# Steppers.net
KiCad netlist of a schematic drawn in Altium Designer
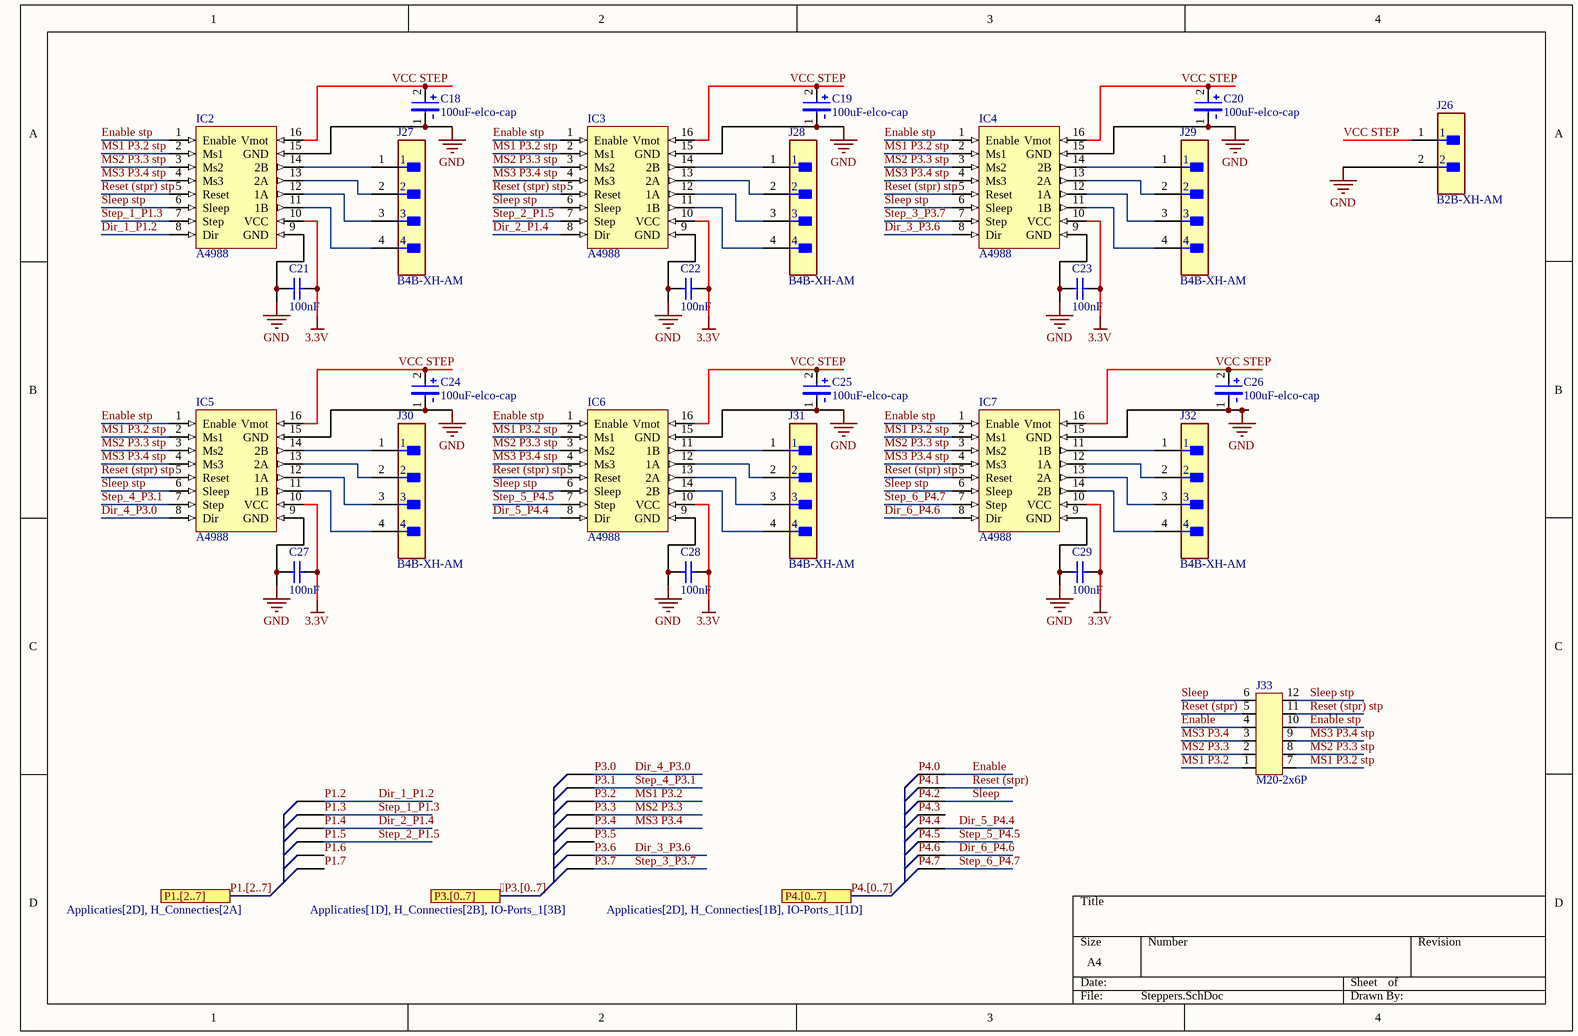
[diagram p0: Steppers.SchDoc]

(export (version "E")
  (design (tool "Eeschema 10.0.6"))
  (components
    (comp (ref "C18")
      (value "100uF-elco-cap")
      (footprint "SMD-ELCO-CAP")
      (description "Max 35V")
      (libsource (lib "Eigen_schemas") (part "100uF-elco-cap"))
    )
    (comp (ref "C19")
      (value "100uF-elco-cap")
      (footprint "SMD-ELCO-CAP")
      (description "Max 35V")
      (libsource (lib "Eigen_schemas") (part "100uF-elco-cap"))
    )
    (comp (ref "C20")
      (value "100uF-elco-cap")
      (footprint "SMD-ELCO-CAP")
      (description "Max 35V")
      (libsource (lib "Eigen_schemas") (part "100uF-elco-cap"))
    )
    (comp (ref "C21")
      (value "100nF")
      (footprint "CAPC1608X90X35LL15T15")
      (fields
        (field (name "MANUFACTURER") "AVX Interconnect / Elco")
        (field (name "PART NUMBER") "0603ZC101KAT2A")
      )
      (libsource (lib "Altium Content Vault") (part "CAP"))
    )
    (comp (ref "C22")
      (value "100nF")
      (footprint "CAPC1608X90X35LL15T15")
      (fields
        (field (name "MANUFACTURER") "AVX Interconnect / Elco")
        (field (name "PART NUMBER") "0603ZC101KAT2A")
      )
      (libsource (lib "Altium Content Vault") (part "CAP"))
    )
    (comp (ref "C23")
      (value "100nF")
      (footprint "CAPC1608X90X35LL15T15")
      (fields
        (field (name "MANUFACTURER") "AVX Interconnect / Elco")
        (field (name "PART NUMBER") "0603ZC101KAT2A")
      )
      (libsource (lib "Altium Content Vault") (part "CAP"))
    )
    (comp (ref "C24")
      (value "100uF-elco-cap")
      (footprint "SMD-ELCO-CAP")
      (description "Max 35V")
      (libsource (lib "Eigen_schemas") (part "100uF-elco-cap"))
    )
    (comp (ref "C25")
      (value "100uF-elco-cap")
      (footprint "SMD-ELCO-CAP")
      (description "Max 35V")
      (libsource (lib "Eigen_schemas") (part "100uF-elco-cap"))
    )
    (comp (ref "C26")
      (value "100uF-elco-cap")
      (footprint "SMD-ELCO-CAP")
      (description "Max 35V")
      (libsource (lib "Eigen_schemas") (part "100uF-elco-cap"))
    )
    (comp (ref "C27")
      (value "100nF")
      (footprint "CAPC1608X90X35LL15T15")
      (fields
        (field (name "MANUFACTURER") "AVX Interconnect / Elco")
        (field (name "PART NUMBER") "0603ZC101KAT2A")
      )
      (libsource (lib "Altium Content Vault") (part "CAP"))
    )
    (comp (ref "C28")
      (value "100nF")
      (footprint "CAPC1608X90X35LL15T15")
      (fields
        (field (name "MANUFACTURER") "AVX Interconnect / Elco")
        (field (name "PART NUMBER") "0603ZC101KAT2A")
      )
      (libsource (lib "Altium Content Vault") (part "CAP"))
    )
    (comp (ref "C29")
      (value "100nF")
      (footprint "CAPC1608X90X35LL15T15")
      (fields
        (field (name "MANUFACTURER") "AVX Interconnect / Elco")
        (field (name "PART NUMBER") "0603ZC101KAT2A")
      )
      (libsource (lib "Altium Content Vault") (part "CAP"))
    )
    (comp (ref "IC2")
      (value "A4988")
      (footprint "A4988")
      (description "stappenmotor driver")
      (libsource (lib "Eigen_schemas") (part "A4988"))
    )
    (comp (ref "IC3")
      (value "A4988")
      (footprint "A4988")
      (description "stappenmotor driver")
      (libsource (lib "Eigen_schemas") (part "A4988"))
    )
    (comp (ref "IC4")
      (value "A4988")
      (footprint "A4988")
      (description "stappenmotor driver")
      (libsource (lib "Eigen_schemas") (part "A4988"))
    )
    (comp (ref "IC5")
      (value "A4988")
      (footprint "A4988")
      (description "stappenmotor driver")
      (libsource (lib "Eigen_schemas") (part "A4988"))
    )
    (comp (ref "IC6")
      (value "A4988")
      (footprint "A4988")
      (description "stappenmotor driver")
      (libsource (lib "") (part "A4988_1"))
    )
    (comp (ref "IC7")
      (value "A4988")
      (footprint "A4988")
      (description "stappenmotor driver")
      (libsource (lib "") (part "A4988_1"))
    )
    (comp (ref "J26")
      (value "B2B-XH-AM")
      (footprint "FP-B2B-XH-AM_LF_SN-MFG")
      (description "CONN HEADER VERT 2POS 2.5MM")
      (libsource (lib "Altium Content Vault") (part "3bc925449376181038e59eaffc5286c"))
    )
    (comp (ref "J27")
      (value "B4B-XH-AM")
      (footprint "FP-B4B-XH-A_LF_SN-MFG")
      (description "CONN HEADER VERT 4POS 2.5MM")
      (libsource (lib "Altium Content Vault") (part "299a8cea1bdcbc3624fe62c390fa72c"))
    )
    (comp (ref "J28")
      (value "B4B-XH-AM")
      (footprint "FP-B4B-XH-A_LF_SN-MFG")
      (description "CONN HEADER VERT 4POS 2.5MM")
      (libsource (lib "Altium Content Vault") (part "299a8cea1bdcbc3624fe62c390fa72c"))
    )
    (comp (ref "J29")
      (value "B4B-XH-AM")
      (footprint "FP-B4B-XH-A_LF_SN-MFG")
      (description "CONN HEADER VERT 4POS 2.5MM")
      (libsource (lib "Altium Content Vault") (part "299a8cea1bdcbc3624fe62c390fa72c"))
    )
    (comp (ref "J30")
      (value "B4B-XH-AM")
      (footprint "FP-B4B-XH-A_LF_SN-MFG")
      (description "CONN HEADER VERT 4POS 2.5MM")
      (libsource (lib "Altium Content Vault") (part "299a8cea1bdcbc3624fe62c390fa72c"))
    )
    (comp (ref "J31")
      (value "B4B-XH-AM")
      (footprint "FP-B4B-XH-A_LF_SN-MFG")
      (description "CONN HEADER VERT 4POS 2.5MM")
      (libsource (lib "Altium Content Vault") (part "299a8cea1bdcbc3624fe62c390fa72c"))
    )
    (comp (ref "J32")
      (value "B4B-XH-AM")
      (footprint "FP-B4B-XH-A_LF_SN-MFG")
      (description "CONN HEADER VERT 4POS 2.5MM")
      (libsource (lib "Altium Content Vault") (part "299a8cea1bdcbc3624fe62c390fa72c"))
    )
    (comp (ref "J33")
      (value "M20-2x6P")
      (footprint "M20-2x6PIN")
      (libsource (lib "Eigen_schemas") (part "M20-2x6P"))
    )
  )
  (nets
    (net (code "9") (name "/P3.0") (class "Default")
      (node (ref "IC5") (pin "8") (pinfunction "Dir_8") (pintype "input"))
    )
    (net (code "10") (name "/P3.1") (class "Default")
      (node (ref "IC5") (pin "7") (pinfunction "Step_7") (pintype "input"))
    )
    (net (code "11") (name "/P3.2") (class "Default")
      (node (ref "J33") (pin "1") (pinfunction "9_1") (pintype "passive"))
    )
    (net (code "12") (name "/P3.3") (class "Default")
      (node (ref "J33") (pin "2") (pinfunction "10_2") (pintype "passive"))
    )
    (net (code "13") (name "/P3.4") (class "Default")
      (node (ref "J33") (pin "3") (pinfunction "11_3") (pintype "passive"))
    )
    (net (code "15") (name "/P3.6") (class "Default")
      (node (ref "IC4") (pin "8") (pinfunction "Dir_8") (pintype "input"))
    )
    (net (code "16") (name "/P3.7") (class "Default")
      (node (ref "IC4") (pin "7") (pinfunction "Step_7") (pintype "input"))
    )
    (net (code "18") (name "/Enable stp") (class "Default")
      (node (ref "IC2") (pin "1") (pinfunction "Enable_1") (pintype "input"))
      (node (ref "IC3") (pin "1") (pinfunction "Enable_1") (pintype "input"))
      (node (ref "IC4") (pin "1") (pinfunction "Enable_1") (pintype "input"))
      (node (ref "IC5") (pin "1") (pinfunction "Enable_1") (pintype "input"))
      (node (ref "IC6") (pin "1") (pinfunction "Enable_1") (pintype "input"))
      (node (ref "IC7") (pin "1") (pinfunction "Enable_1") (pintype "input"))
      (node (ref "J33") (pin "10") (pinfunction "10_10") (pintype "passive"))
    )
    (net (code "19") (name "/MS1 P3.2 stp") (class "Default")
      (node (ref "IC2") (pin "2") (pinfunction "Ms1_2") (pintype "input"))
      (node (ref "IC3") (pin "2") (pinfunction "Ms1_2") (pintype "input"))
      (node (ref "IC4") (pin "2") (pinfunction "Ms1_2") (pintype "input"))
      (node (ref "IC5") (pin "2") (pinfunction "Ms1_2") (pintype "input"))
      (node (ref "IC6") (pin "2") (pinfunction "Ms1_2") (pintype "input"))
      (node (ref "IC7") (pin "2") (pinfunction "Ms1_2") (pintype "input"))
      (node (ref "J33") (pin "7") (pinfunction "7_7") (pintype "passive"))
    )
    (net (code "20") (name "/MS2 P3.3 stp") (class "Default")
      (node (ref "IC2") (pin "3") (pinfunction "Ms2_3") (pintype "input"))
      (node (ref "IC3") (pin "3") (pinfunction "Ms2_3") (pintype "input"))
      (node (ref "IC4") (pin "3") (pinfunction "Ms2_3") (pintype "input"))
      (node (ref "IC5") (pin "3") (pinfunction "Ms2_3") (pintype "input"))
      (node (ref "IC6") (pin "3") (pinfunction "Ms2_3") (pintype "input"))
      (node (ref "IC7") (pin "3") (pinfunction "Ms2_3") (pintype "input"))
      (node (ref "J33") (pin "8") (pinfunction "8_8") (pintype "passive"))
    )
    (net (code "21") (name "/MS3 P3.4 stp") (class "Default")
      (node (ref "IC2") (pin "4") (pinfunction "Ms3_4") (pintype "input"))
      (node (ref "IC3") (pin "4") (pinfunction "Ms3_4") (pintype "input"))
      (node (ref "IC4") (pin "4") (pinfunction "Ms3_4") (pintype "input"))
      (node (ref "IC5") (pin "4") (pinfunction "Ms3_4") (pintype "input"))
      (node (ref "IC6") (pin "4") (pinfunction "Ms3_4") (pintype "input"))
      (node (ref "IC7") (pin "4") (pinfunction "Ms3_4") (pintype "input"))
      (node (ref "J33") (pin "9") (pinfunction "9_9") (pintype "passive"))
    )
    (net (code "22") (name "/P1.2") (class "Default")
      (node (ref "IC2") (pin "8") (pinfunction "Dir_8") (pintype "input"))
    )
    (net (code "23") (name "/P1.3") (class "Default")
      (node (ref "IC2") (pin "7") (pinfunction "Step_7") (pintype "input"))
    )
    (net (code "24") (name "/P1.4") (class "Default")
      (node (ref "IC3") (pin "8") (pinfunction "Dir_8") (pintype "input"))
    )
    (net (code "25") (name "/P1.5") (class "Default")
      (node (ref "IC3") (pin "7") (pinfunction "Step_7") (pintype "input"))
    )
    (net (code "29") (name "/P4.0") (class "Default")
      (node (ref "J33") (pin "4") (pinfunction "12_4") (pintype "passive"))
    )
    (net (code "30") (name "/P4.1") (class "Default")
      (node (ref "J33") (pin "5") (pinfunction "13_5") (pintype "passive"))
    )
    (net (code "31") (name "/P4.2") (class "Default")
      (node (ref "J33") (pin "6") (pinfunction "14_6") (pintype "passive"))
    )
    (net (code "33") (name "/P4.4") (class "Default")
      (node (ref "IC6") (pin "8") (pinfunction "Dir_8") (pintype "input"))
    )
    (net (code "34") (name "/P4.5") (class "Default")
      (node (ref "IC6") (pin "7") (pinfunction "Step_7") (pintype "input"))
    )
    (net (code "35") (name "/P4.6") (class "Default")
      (node (ref "IC7") (pin "8") (pinfunction "Dir_8") (pintype "input"))
    )
    (net (code "36") (name "/P4.7") (class "Default")
      (node (ref "IC7") (pin "7") (pinfunction "Step_7") (pintype "input"))
    )
    (net (code "38") (name "/Reset (stpr) stp") (class "Default")
      (node (ref "IC2") (pin "5") (pinfunction "Reset_5") (pintype "input"))
      (node (ref "IC3") (pin "5") (pinfunction "Reset_5") (pintype "input"))
      (node (ref "IC4") (pin "5") (pinfunction "Reset_5") (pintype "input"))
      (node (ref "IC5") (pin "5") (pinfunction "Reset_5") (pintype "input"))
      (node (ref "IC6") (pin "5") (pinfunction "Reset_5") (pintype "input"))
      (node (ref "IC7") (pin "5") (pinfunction "Reset_5") (pintype "input"))
      (node (ref "J33") (pin "11") (pinfunction "11_11") (pintype "passive"))
    )
    (net (code "39") (name "/Sleep stp") (class "Default")
      (node (ref "IC2") (pin "6") (pinfunction "Sleep_6") (pintype "input"))
      (node (ref "IC3") (pin "6") (pinfunction "Sleep_6") (pintype "input"))
      (node (ref "IC4") (pin "6") (pinfunction "Sleep_6") (pintype "input"))
      (node (ref "IC5") (pin "6") (pinfunction "Sleep_6") (pintype "input"))
      (node (ref "IC6") (pin "6") (pinfunction "Sleep_6") (pintype "input"))
      (node (ref "IC7") (pin "6") (pinfunction "Sleep_6") (pintype "input"))
      (node (ref "J33") (pin "12") (pinfunction "12_12") (pintype "passive"))
    )
    (net (code "40") (name "/VCC STEP") (class "Default")
      (node (ref "C18") (pin "2") (pinfunction "5_2") (pintype "passive"))
      (node (ref "C19") (pin "2") (pinfunction "5_2") (pintype "passive"))
      (node (ref "C20") (pin "2") (pinfunction "5_2") (pintype "passive"))
      (node (ref "C24") (pin "2") (pinfunction "5_2") (pintype "passive"))
      (node (ref "C25") (pin "2") (pinfunction "5_2") (pintype "passive"))
      (node (ref "C26") (pin "2") (pinfunction "5_2") (pintype "passive"))
      (node (ref "IC2") (pin "16") (pinfunction "Vmot_16") (pintype "input"))
      (node (ref "IC3") (pin "16") (pinfunction "Vmot_16") (pintype "input"))
      (node (ref "IC4") (pin "16") (pinfunction "Vmot_16") (pintype "input"))
      (node (ref "IC5") (pin "16") (pinfunction "Vmot_16") (pintype "input"))
      (node (ref "IC6") (pin "16") (pinfunction "Vmot_16") (pintype "input"))
      (node (ref "IC7") (pin "16") (pinfunction "Vmot_16") (pintype "input"))
      (node (ref "J26") (pin "1") (pinfunction "1_1") (pintype "passive"))
    )
    (net (code "41") (name "3.3V") (class "Default")
      (node (ref "C21") (pin "1") (pinfunction "1_1") (pintype "passive"))
      (node (ref "C22") (pin "1") (pinfunction "1_1") (pintype "passive"))
      (node (ref "C23") (pin "1") (pinfunction "1_1") (pintype "passive"))
      (node (ref "C27") (pin "1") (pinfunction "1_1") (pintype "passive"))
      (node (ref "C28") (pin "1") (pinfunction "1_1") (pintype "passive"))
      (node (ref "C29") (pin "1") (pinfunction "1_1") (pintype "passive"))
      (node (ref "IC2") (pin "10") (pinfunction "VCC_10") (pintype "input"))
      (node (ref "IC3") (pin "10") (pinfunction "VCC_10") (pintype "input"))
      (node (ref "IC4") (pin "10") (pinfunction "VCC_10") (pintype "input"))
      (node (ref "IC5") (pin "10") (pinfunction "VCC_10") (pintype "input"))
      (node (ref "IC6") (pin "10") (pinfunction "VCC_10") (pintype "input"))
      (node (ref "IC7") (pin "10") (pinfunction "VCC_10") (pintype "input"))
    )
    (net (code "42") (name "GND") (class "Default")
      (node (ref "C18") (pin "1") (pinfunction "4_1") (pintype "passive"))
      (node (ref "C19") (pin "1") (pinfunction "4_1") (pintype "passive"))
      (node (ref "C20") (pin "1") (pinfunction "4_1") (pintype "passive"))
      (node (ref "C21") (pin "2") (pinfunction "2_2") (pintype "passive"))
      (node (ref "C22") (pin "2") (pinfunction "2_2") (pintype "passive"))
      (node (ref "C23") (pin "2") (pinfunction "2_2") (pintype "passive"))
      (node (ref "C24") (pin "1") (pinfunction "4_1") (pintype "passive"))
      (node (ref "C25") (pin "1") (pinfunction "4_1") (pintype "passive"))
      (node (ref "C26") (pin "1") (pinfunction "4_1") (pintype "passive"))
      (node (ref "C27") (pin "2") (pinfunction "2_2") (pintype "passive"))
      (node (ref "C28") (pin "2") (pinfunction "2_2") (pintype "passive"))
      (node (ref "C29") (pin "2") (pinfunction "2_2") (pintype "passive"))
      (node (ref "IC2") (pin "15") (pinfunction "GND_15") (pintype "input"))
      (node (ref "IC2") (pin "9") (pinfunction "GND_9") (pintype "input"))
      (node (ref "IC3") (pin "15") (pinfunction "GND_15") (pintype "input"))
      (node (ref "IC3") (pin "9") (pinfunction "GND_9") (pintype "input"))
      (node (ref "IC4") (pin "15") (pinfunction "GND_15") (pintype "input"))
      (node (ref "IC4") (pin "9") (pinfunction "GND_9") (pintype "input"))
      (node (ref "IC5") (pin "15") (pinfunction "GND_15") (pintype "input"))
      (node (ref "IC5") (pin "9") (pinfunction "GND_9") (pintype "input"))
      (node (ref "IC6") (pin "15") (pinfunction "GND_15") (pintype "input"))
      (node (ref "IC6") (pin "9") (pinfunction "GND_9") (pintype "input"))
      (node (ref "IC7") (pin "15") (pinfunction "GND_15") (pintype "input"))
      (node (ref "IC7") (pin "9") (pinfunction "GND_9") (pintype "input"))
      (node (ref "J26") (pin "2") (pinfunction "2_2") (pintype "passive"))
    )
    (net (code "43") (name "Net-(IC2-1A)") (class "Default")
      (node (ref "IC2") (pin "12") (pinfunction "1A_12") (pintype "output"))
      (node (ref "J27") (pin "3") (pinfunction "3_3") (pintype "passive"))
    )
    (net (code "44") (name "Net-(IC2-1B)") (class "Default")
      (node (ref "IC2") (pin "11") (pinfunction "1B_11") (pintype "output"))
      (node (ref "J27") (pin "4") (pinfunction "4_4") (pintype "passive"))
    )
    (net (code "45") (name "Net-(IC2-2A)") (class "Default")
      (node (ref "IC2") (pin "13") (pinfunction "2A_13") (pintype "output"))
      (node (ref "J27") (pin "2") (pinfunction "2_2") (pintype "passive"))
    )
    (net (code "46") (name "Net-(IC2-2B)") (class "Default")
      (node (ref "IC2") (pin "14") (pinfunction "2B_14") (pintype "output"))
      (node (ref "J27") (pin "1") (pinfunction "1_1") (pintype "passive"))
    )
    (net (code "47") (name "Net-(IC3-1A)") (class "Default")
      (node (ref "IC3") (pin "12") (pinfunction "1A_12") (pintype "output"))
      (node (ref "J28") (pin "3") (pinfunction "3_3") (pintype "passive"))
    )
    (net (code "48") (name "Net-(IC3-1B)") (class "Default")
      (node (ref "IC3") (pin "11") (pinfunction "1B_11") (pintype "output"))
      (node (ref "J28") (pin "4") (pinfunction "4_4") (pintype "passive"))
    )
    (net (code "49") (name "Net-(IC3-2A)") (class "Default")
      (node (ref "IC3") (pin "13") (pinfunction "2A_13") (pintype "output"))
      (node (ref "J28") (pin "2") (pinfunction "2_2") (pintype "passive"))
    )
    (net (code "50") (name "Net-(IC3-2B)") (class "Default")
      (node (ref "IC3") (pin "14") (pinfunction "2B_14") (pintype "output"))
      (node (ref "J28") (pin "1") (pinfunction "1_1") (pintype "passive"))
    )
    (net (code "51") (name "Net-(IC4-1A)") (class "Default")
      (node (ref "IC4") (pin "12") (pinfunction "1A_12") (pintype "output"))
      (node (ref "J29") (pin "3") (pinfunction "3_3") (pintype "passive"))
    )
    (net (code "52") (name "Net-(IC4-1B)") (class "Default")
      (node (ref "IC4") (pin "11") (pinfunction "1B_11") (pintype "output"))
      (node (ref "J29") (pin "4") (pinfunction "4_4") (pintype "passive"))
    )
    (net (code "53") (name "Net-(IC4-2A)") (class "Default")
      (node (ref "IC4") (pin "13") (pinfunction "2A_13") (pintype "output"))
      (node (ref "J29") (pin "2") (pinfunction "2_2") (pintype "passive"))
    )
    (net (code "54") (name "Net-(IC4-2B)") (class "Default")
      (node (ref "IC4") (pin "14") (pinfunction "2B_14") (pintype "output"))
      (node (ref "J29") (pin "1") (pinfunction "1_1") (pintype "passive"))
    )
    (net (code "55") (name "Net-(IC5-1A)") (class "Default")
      (node (ref "IC5") (pin "12") (pinfunction "1A_12") (pintype "output"))
      (node (ref "J30") (pin "3") (pinfunction "3_3") (pintype "passive"))
    )
    (net (code "56") (name "Net-(IC5-1B)") (class "Default")
      (node (ref "IC5") (pin "11") (pinfunction "1B_11") (pintype "output"))
      (node (ref "J30") (pin "4") (pinfunction "4_4") (pintype "passive"))
    )
    (net (code "57") (name "Net-(IC5-2A)") (class "Default")
      (node (ref "IC5") (pin "13") (pinfunction "2A_13") (pintype "output"))
      (node (ref "J30") (pin "2") (pinfunction "2_2") (pintype "passive"))
    )
    (net (code "58") (name "Net-(IC5-2B)") (class "Default")
      (node (ref "IC5") (pin "14") (pinfunction "2B_14") (pintype "output"))
      (node (ref "J30") (pin "1") (pinfunction "1_1") (pintype "passive"))
    )
    (net (code "59") (name "Net-(IC6-1A)") (class "Default")
      (node (ref "IC6") (pin "12") (pinfunction "1A_12") (pintype "output"))
      (node (ref "J31") (pin "2") (pinfunction "2_2") (pintype "passive"))
    )
    (net (code "60") (name "Net-(IC6-1B)") (class "Default")
      (node (ref "IC6") (pin "11") (pinfunction "1B_11") (pintype "output"))
      (node (ref "J31") (pin "1") (pinfunction "1_1") (pintype "passive"))
    )
    (net (code "61") (name "Net-(IC6-2A)") (class "Default")
      (node (ref "IC6") (pin "13") (pinfunction "2A_13") (pintype "output"))
      (node (ref "J31") (pin "3") (pinfunction "3_3") (pintype "passive"))
    )
    (net (code "62") (name "Net-(IC6-2B)") (class "Default")
      (node (ref "IC6") (pin "14") (pinfunction "2B_14") (pintype "output"))
      (node (ref "J31") (pin "4") (pinfunction "4_4") (pintype "passive"))
    )
    (net (code "63") (name "Net-(IC7-1A)") (class "Default")
      (node (ref "IC7") (pin "12") (pinfunction "1A_12") (pintype "output"))
      (node (ref "J32") (pin "2") (pinfunction "2_2") (pintype "passive"))
    )
    (net (code "64") (name "Net-(IC7-1B)") (class "Default")
      (node (ref "IC7") (pin "11") (pinfunction "1B_11") (pintype "output"))
      (node (ref "J32") (pin "1") (pinfunction "1_1") (pintype "passive"))
    )
    (net (code "65") (name "Net-(IC7-2A)") (class "Default")
      (node (ref "IC7") (pin "13") (pinfunction "2A_13") (pintype "output"))
      (node (ref "J32") (pin "3") (pinfunction "3_3") (pintype "passive"))
    )
    (net (code "66") (name "Net-(IC7-2B)") (class "Default")
      (node (ref "IC7") (pin "14") (pinfunction "2B_14") (pintype "output"))
      (node (ref "J32") (pin "4") (pinfunction "4_4") (pintype "passive"))
    )
  )
)
